# geiger-board.net
KiCad netlist of a schematic drawn in EAGLE
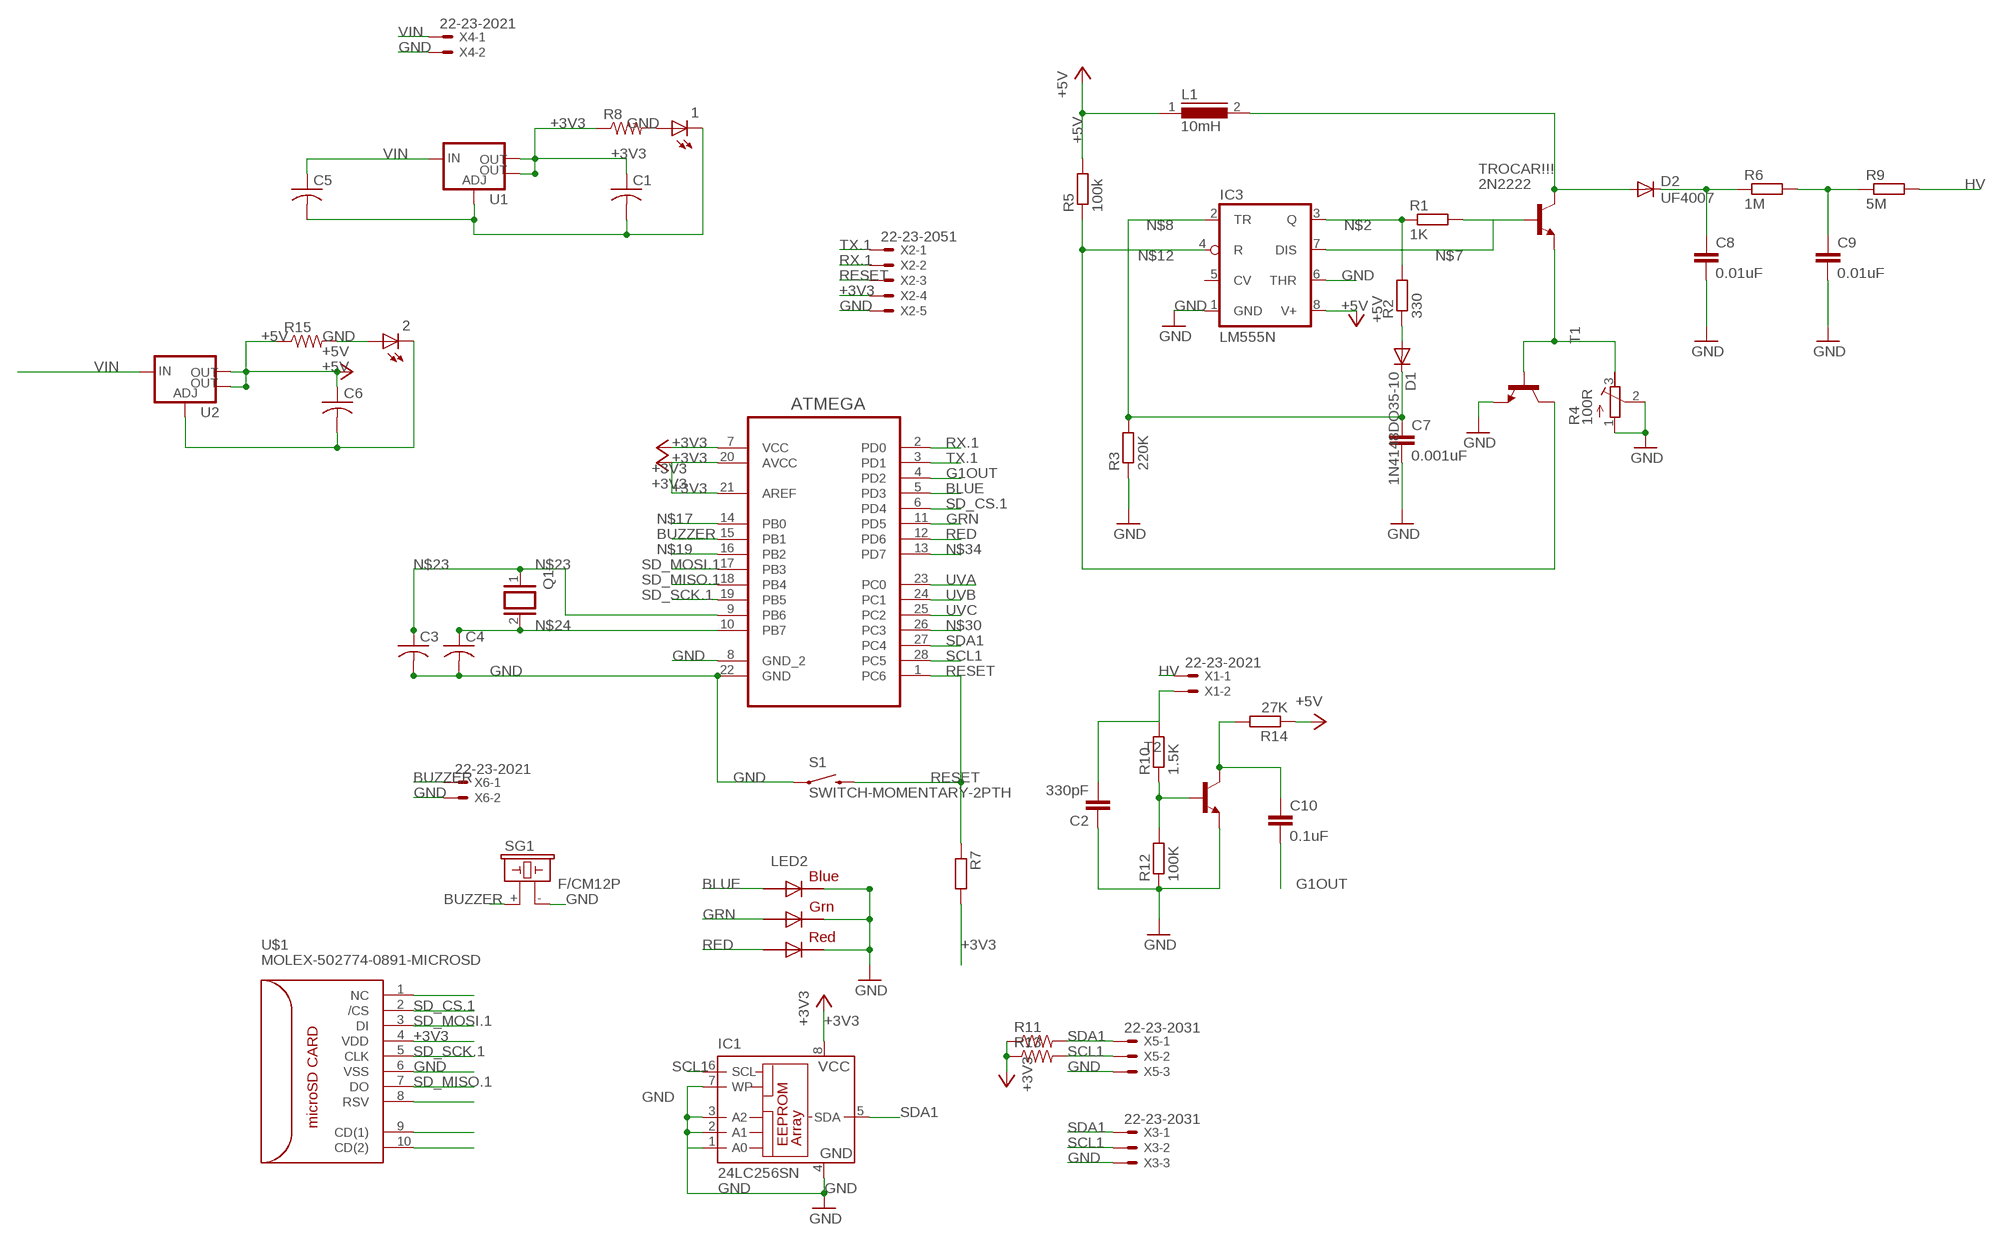
[diagram p0: schematic, sheet 1]

(export (version "E")
  (design (tool "Eeschema 10.0.6"))
  (components
    (comp (ref "1")
      (value "LEDSMT1206")
      (footprint "eagle-import:1206")
      (libsource (lib "eagle-import") (part "LEDSMT1206"))
    )
    (comp (ref "2")
      (value "LEDSMT1206")
      (footprint "eagle-import:1206")
      (libsource (lib "eagle-import") (part "LEDSMT1206"))
    )
    (comp (ref "ATMEGA")
      (value "ATMEGA328P-PU")
      (footprint "eagle-import:DIP254P762X457-28")
      (libsource (lib "eagle-import") (part "ATMEGA328P-PU"))
    )
    (comp (ref "C1")
      (value "C-USC1210K")
      (footprint "eagle-import:C1210K")
      (libsource (lib "eagle-import") (part "C-USC1210K"))
    )
    (comp (ref "C2")
      (value "330pF")
      (footprint "eagle-import:C5B4.5")
      (libsource (lib "eagle-import") (part "C5/4.5"))
    )
    (comp (ref "C3")
      (value "C-USC1210K")
      (footprint "eagle-import:C1210K")
      (libsource (lib "eagle-import") (part "C-USC1210K"))
    )
    (comp (ref "C4")
      (value "C-USC1210K")
      (footprint "eagle-import:C1210K")
      (libsource (lib "eagle-import") (part "C-USC1210K"))
    )
    (comp (ref "C5")
      (value "C-USC1210K")
      (footprint "eagle-import:C1210K")
      (libsource (lib "eagle-import") (part "C-USC1210K"))
    )
    (comp (ref "C6")
      (value "C-USC1210K")
      (footprint "eagle-import:C1210K")
      (libsource (lib "eagle-import") (part "C-USC1210K"))
    )
    (comp (ref "C7")
      (value "0.001uF")
      (footprint "eagle-import:C5B4.5")
      (libsource (lib "eagle-import") (part "C5/4.5"))
    )
    (comp (ref "C8")
      (value "0.01uF")
      (footprint "eagle-import:C5B4.5")
      (libsource (lib "eagle-import") (part "C5/4.5"))
    )
    (comp (ref "C9")
      (value "0.01uF")
      (footprint "eagle-import:C5B4.5")
      (libsource (lib "eagle-import") (part "C5/4.5"))
    )
    (comp (ref "C10")
      (value "0.1uF")
      (footprint "eagle-import:C5B4.5")
      (libsource (lib "eagle-import") (part "C5/4.5"))
    )
    (comp (ref "D1")
      (value "1N4148DO35-10")
      (footprint "eagle-import:DO35-10")
      (libsource (lib "eagle-import") (part "1N4148DO35-10"))
    )
    (comp (ref "D2")
      (value "UF4007")
      (footprint "eagle-import:DO35-10")
      (libsource (lib "eagle-import") (part "1N4148DO35-10"))
    )
    (comp (ref "IC1")
      (value "24LC256SN")
      (footprint "eagle-import:SO-08")
      (fields (field (name "MF") "MICROCHIP") (field (name "MPN") "24LC256-I/SN"))
      (libsource (lib "eagle-import") (part "24SNLC256"))
    )
    (comp (ref "IC3")
      (value "LM555N")
      (footprint "eagle-import:DIL08-ROUND")
      (libsource (lib "eagle-import") (part "555NLM"))
    )
    (comp (ref "L1")
      (value "10mH")
      (footprint "eagle-import:82114R")
      (libsource (lib "eagle-import") (part "82114R"))
    )
    (comp (ref "LED2")
      (value "RGBLED5050")
      (footprint "eagle-import:RGBLED5050")
      (libsource (lib "eagle-import") (part "RGBLED5050"))
    )
    (comp (ref "Q1")
      (value "XTAL/S")
      (footprint "eagle-import:QS")
      (libsource (lib "eagle-import") (part "XTAL/S"))
    )
    (comp (ref "R1")
      (value "1K")
      (footprint "eagle-import:0207_10")
      (libsource (lib "eagle-import") (part "R0207/10"))
    )
    (comp (ref "R2")
      (value "330")
      (footprint "eagle-import:0207_10")
      (libsource (lib "eagle-import") (part "R0207/10"))
    )
    (comp (ref "R3")
      (value "220K")
      (footprint "eagle-import:0207_10")
      (libsource (lib "eagle-import") (part "R0207/10"))
    )
    (comp (ref "R4")
      (value "100R")
      (footprint "eagle-import:RTRIM3296W")
      (libsource (lib "eagle-import") (part "R-TRIMM3296W"))
    )
    (comp (ref "R5")
      (value "100k")
      (footprint "eagle-import:0207_10")
      (libsource (lib "eagle-import") (part "R0207/10"))
    )
    (comp (ref "R6")
      (value "1M")
      (footprint "eagle-import:0207_10")
      (libsource (lib "eagle-import") (part "R0207/10"))
    )
    (comp (ref "R7")
      (value "R-EU_0207/10")
      (footprint "eagle-import:0207_10")
      (libsource (lib "eagle-import") (part "R-EU_0207/10"))
    )
    (comp (ref "R8")
      (value "R-US_M1206")
      (footprint "eagle-import:M1206")
      (libsource (lib "eagle-import") (part "R-US_M1206"))
    )
    (comp (ref "R9")
      (value "5M")
      (footprint "eagle-import:0207_10")
      (libsource (lib "eagle-import") (part "R0207/10"))
    )
    (comp (ref "R10")
      (value "1.5K")
      (footprint "eagle-import:0207_10")
      (libsource (lib "eagle-import") (part "R0207/10"))
    )
    (comp (ref "R11")
      (value "R-US_R1206")
      (footprint "eagle-import:R1206")
      (libsource (lib "eagle-import") (part "R-US_R1206"))
    )
    (comp (ref "R12")
      (value "100K")
      (footprint "eagle-import:0207_10")
      (libsource (lib "eagle-import") (part "R0207/10"))
    )
    (comp (ref "R13")
      (value "R-US_R1206")
      (footprint "eagle-import:R1206")
      (libsource (lib "eagle-import") (part "R-US_R1206"))
    )
    (comp (ref "R14")
      (value "27K")
      (footprint "eagle-import:0207_10")
      (libsource (lib "eagle-import") (part "R0207/10"))
    )
    (comp (ref "R15")
      (value "R-US_M1206")
      (footprint "eagle-import:M1206")
      (libsource (lib "eagle-import") (part "R-US_M1206"))
    )
    (comp (ref "S1")
      (value "SWITCH-MOMENTARY-2PTH")
      (footprint "eagle-import:TACTILE-PTH")
      (libsource (lib "eagle-import") (part "SWITCH-MOMENTARY-2PTH"))
    )
    (comp (ref "SG1")
      (value "F/CM12P")
      (footprint "eagle-import:F_CM12P")
      (libsource (lib "eagle-import") (part "F/CM12P"))
    )
    (comp (ref "T1")
      (value "2N4401-NPN-TO92-EBC")
      (footprint "eagle-import:TO92-EBC")
      (libsource (lib "eagle-import") (part "-NPN-TO92-EBC2N4401"))
    )
    (comp (ref "T2")
      (value "2N4401-NPN-TO92-EBC")
      (footprint "eagle-import:TO92-EBC")
      (libsource (lib "eagle-import") (part "-NPN-TO92-EBC2N4401"))
    )
    (comp (ref "TROCAR!!!")
      (value "2N2222")
      (footprint "eagle-import:TO92-EBC-OVAL")
      (libsource (lib "eagle-import") (part "2N2222"))
    )
    (comp (ref "U$1")
      (value "MOLEX-502774-0891-MICROSD")
      (footprint "eagle-import:MOLEX-502774-0891-MICROSD")
      (libsource (lib "eagle-import") (part "MOLEX-502774-0891-MICROSD"))
    )
    (comp (ref "U1")
      (value "V_REG_LM1117SOT223")
      (footprint "eagle-import:SOT223")
      (libsource (lib "eagle-import") (part "V_REG_LM1117SOT223"))
    )
    (comp (ref "U2")
      (value "V_REG_LM1117SOT223")
      (footprint "eagle-import:SOT223")
      (libsource (lib "eagle-import") (part "V_REG_LM1117SOT223"))
    )
    (comp (ref "X1")
      (value "22-23-2021")
      (footprint "eagle-import:22-23-2021")
      (fields (field (name "MF") "MOLEX"))
      (libsource (lib "eagle-import") (part "22-23-2021"))
    )
    (comp (ref "X2")
      (value "22-23-2051")
      (footprint "eagle-import:22-23-2051")
      (fields (field (name "MF") "MOLEX"))
      (libsource (lib "eagle-import") (part "22-23-2051"))
    )
    (comp (ref "X3")
      (value "22-23-2031")
      (footprint "eagle-import:22-23-2031")
      (fields (field (name "MF") "MOLEX"))
      (libsource (lib "eagle-import") (part "22-23-2031"))
    )
    (comp (ref "X4")
      (value "22-23-2021")
      (footprint "eagle-import:22-23-2021")
      (fields (field (name "MF") "MOLEX"))
      (libsource (lib "eagle-import") (part "22-23-2021"))
    )
    (comp (ref "X5")
      (value "22-23-2031")
      (footprint "eagle-import:22-23-2031")
      (fields (field (name "MF") "MOLEX"))
      (libsource (lib "eagle-import") (part "22-23-2031"))
    )
    (comp (ref "X6")
      (value "22-23-2021")
      (footprint "eagle-import:22-23-2021")
      (fields (field (name "MF") "MOLEX"))
      (libsource (lib "eagle-import") (part "22-23-2021"))
    )
  )
  (nets
    (net (code "1") (name "+3V3") (class "Default")
      (node (ref "ATMEGA") (pin "20") (pinfunction "AVCC_20") (pintype "power_in"))
      (node (ref "ATMEGA") (pin "21") (pinfunction "AREF_21") (pintype "input"))
      (node (ref "ATMEGA") (pin "7") (pinfunction "VCC_7") (pintype "power_in"))
      (node (ref "C1") (pin "1") (pinfunction "1_1") (pintype "passive"))
      (node (ref "IC1") (pin "8") (pinfunction "VCC_8") (pintype "power_in"))
      (node (ref "R11") (pin "1") (pinfunction "1_1") (pintype "passive"))
      (node (ref "R13") (pin "1") (pinfunction "1_1") (pintype "passive"))
      (node (ref "R7") (pin "2") (pinfunction "2_2") (pintype "passive"))
      (node (ref "R8") (pin "1") (pinfunction "1_1") (pintype "passive"))
      (node (ref "U$1") (pin "4") (pinfunction "VDD_4") (pintype "bidirectional"))
      (node (ref "U1") (pin "2") (pinfunction "OUT_2") (pintype "output"))
      (node (ref "U1") (pin "4") (pinfunction "OUT_4") (pintype "output"))
      (node (ref "X2") (pin "4") (pinfunction "S_4") (pintype "passive"))
    )
    (net (code "2") (name "+5V") (class "Default")
      (node (ref "C6") (pin "1") (pinfunction "1_1") (pintype "passive"))
      (node (ref "IC3") (pin "8") (pinfunction "V+_8") (pintype "power_in"))
      (node (ref "L1") (pin "1") (pinfunction "1_1") (pintype "passive"))
      (node (ref "R14") (pin "1") (pinfunction "1_1") (pintype "passive"))
      (node (ref "R15") (pin "1") (pinfunction "1_1") (pintype "passive"))
      (node (ref "R5") (pin "2") (pinfunction "2_2") (pintype "passive"))
      (node (ref "U2") (pin "2") (pinfunction "OUT_2") (pintype "output"))
      (node (ref "U2") (pin "4") (pinfunction "OUT_4") (pintype "output"))
    )
    (net (code "3") (name "/BLUE") (class "Default")
      (node (ref "ATMEGA") (pin "5") (pinfunction "PD3_5") (pintype "bidirectional"))
      (node (ref "LED2") (pin "3") (pinfunction "BLUE_A_3") (pintype "bidirectional"))
    )
    (net (code "4") (name "/BUZZER") (class "Default")
      (node (ref "ATMEGA") (pin "15") (pinfunction "PB1_15") (pintype "bidirectional"))
      (node (ref "SG1") (pin "+") (pinfunction "1_+") (pintype "passive"))
      (node (ref "X6") (pin "1") (pinfunction "S_1") (pintype "passive"))
    )
    (net (code "5") (name "/G1OUT") (class "Default")
      (node (ref "ATMEGA") (pin "4") (pinfunction "PD2_4") (pintype "bidirectional"))
      (node (ref "C10") (pin "2") (pinfunction "2_2") (pintype "passive"))
    )
    (net (code "6") (name "/GRN") (class "Default")
      (node (ref "ATMEGA") (pin "11") (pinfunction "PD5_11") (pintype "bidirectional"))
      (node (ref "LED2") (pin "1") (pinfunction "GREEN_A_1") (pintype "bidirectional"))
    )
    (net (code "7") (name "/HV") (class "Default")
      (node (ref "R9") (pin "2") (pinfunction "2_2") (pintype "passive"))
      (node (ref "X1") (pin "1") (pinfunction "S_1") (pintype "passive"))
    )
    (net (code "8") (name "/N$2") (class "Default")
      (node (ref "IC3") (pin "3") (pinfunction "Q_3") (pintype "output"))
      (node (ref "R1") (pin "1") (pinfunction "1_1") (pintype "passive"))
      (node (ref "R2") (pin "2") (pinfunction "2_2") (pintype "passive"))
    )
    (net (code "9") (name "/N$7") (class "Default")
      (node (ref "IC3") (pin "7") (pinfunction "DIS_7") (pintype "input"))
      (node (ref "R1") (pin "2") (pinfunction "2_2") (pintype "passive"))
      (node (ref "TROCAR!!!") (pin "B") (pinfunction "B_B") (pintype "passive"))
    )
    (net (code "10") (name "/N$8") (class "Default")
      (node (ref "C7") (pin "1") (pinfunction "1_1") (pintype "passive"))
      (node (ref "D1") (pin "C") (pinfunction "C_C") (pintype "passive"))
      (node (ref "IC3") (pin "2") (pinfunction "TR_2") (pintype "input"))
      (node (ref "R3") (pin "2") (pinfunction "2_2") (pintype "passive"))
    )
    (net (code "11") (name "/N$12") (class "Default")
      (node (ref "IC3") (pin "4") (pinfunction "R_4") (pintype "input"))
      (node (ref "R5") (pin "1") (pinfunction "1_1") (pintype "passive"))
      (node (ref "T1") (pin "C") (pinfunction "C_C") (pintype "passive"))
    )
    (net (code "12") (name "/N$17") (class "Default")
      (node (ref "ATMEGA") (pin "14") (pinfunction "PB0_14") (pintype "bidirectional"))
    )
    (net (code "13") (name "/N$19") (class "Default")
      (node (ref "ATMEGA") (pin "16") (pinfunction "PB2_16") (pintype "bidirectional"))
    )
    (net (code "14") (name "/N$23") (class "Default")
      (node (ref "ATMEGA") (pin "9") (pinfunction "PB6_9") (pintype "bidirectional"))
      (node (ref "C3") (pin "1") (pinfunction "1_1") (pintype "passive"))
      (node (ref "Q1") (pin "1") (pinfunction "1_1") (pintype "passive"))
    )
    (net (code "15") (name "/N$24") (class "Default")
      (node (ref "ATMEGA") (pin "10") (pinfunction "PB7_10") (pintype "bidirectional"))
      (node (ref "C4") (pin "1") (pinfunction "1_1") (pintype "passive"))
      (node (ref "Q1") (pin "2") (pinfunction "2_2") (pintype "passive"))
    )
    (net (code "16") (name "/N$30") (class "Default")
      (node (ref "ATMEGA") (pin "26") (pinfunction "PC3_26") (pintype "bidirectional"))
    )
    (net (code "17") (name "/N$34") (class "Default")
      (node (ref "ATMEGA") (pin "13") (pinfunction "PD7_13") (pintype "bidirectional"))
    )
    (net (code "18") (name "/RED") (class "Default")
      (node (ref "ATMEGA") (pin "12") (pinfunction "PD6_12") (pintype "bidirectional"))
      (node (ref "LED2") (pin "2") (pinfunction "RED_A_2") (pintype "bidirectional"))
    )
    (net (code "19") (name "/RESET") (class "Default")
      (node (ref "ATMEGA") (pin "1") (pinfunction "PC6_1") (pintype "bidirectional"))
      (node (ref "R7") (pin "1") (pinfunction "1_1") (pintype "passive"))
      (node (ref "S1") (pin "3") (pinfunction "2_3") (pintype "passive"))
      (node (ref "X2") (pin "3") (pinfunction "S_3") (pintype "passive"))
    )
    (net (code "20") (name "/RX.1") (class "Default")
      (node (ref "ATMEGA") (pin "2") (pinfunction "PD0_2") (pintype "bidirectional"))
      (node (ref "X2") (pin "2") (pinfunction "S_2") (pintype "passive"))
    )
    (net (code "21") (name "/SCL1") (class "Default")
      (node (ref "ATMEGA") (pin "28") (pinfunction "PC5_28") (pintype "bidirectional"))
      (node (ref "IC1") (pin "6") (pinfunction "SCL_6") (pintype "input"))
      (node (ref "R13") (pin "2") (pinfunction "2_2") (pintype "passive"))
      (node (ref "X3") (pin "2") (pinfunction "S_2") (pintype "passive"))
      (node (ref "X5") (pin "2") (pinfunction "S_2") (pintype "passive"))
    )
    (net (code "22") (name "/SDA1") (class "Default")
      (node (ref "ATMEGA") (pin "27") (pinfunction "PC4_27") (pintype "bidirectional"))
      (node (ref "IC1") (pin "5") (pinfunction "SDA_5") (pintype "bidirectional"))
      (node (ref "R11") (pin "2") (pinfunction "2_2") (pintype "passive"))
      (node (ref "X3") (pin "1") (pinfunction "S_1") (pintype "passive"))
      (node (ref "X5") (pin "1") (pinfunction "S_1") (pintype "passive"))
    )
    (net (code "23") (name "/SD_CS.1") (class "Default")
      (node (ref "ATMEGA") (pin "6") (pinfunction "PD4_6") (pintype "bidirectional"))
      (node (ref "U$1") (pin "2") (pinfunction "/CS_2") (pintype "bidirectional"))
    )
    (net (code "24") (name "/SD_MISO.1") (class "Default")
      (node (ref "ATMEGA") (pin "18") (pinfunction "PB4_18") (pintype "bidirectional"))
      (node (ref "U$1") (pin "7") (pinfunction "DO_7") (pintype "bidirectional"))
    )
    (net (code "25") (name "/SD_MOSI.1") (class "Default")
      (node (ref "ATMEGA") (pin "17") (pinfunction "PB3_17") (pintype "bidirectional"))
      (node (ref "U$1") (pin "3") (pinfunction "DI_3") (pintype "bidirectional"))
    )
    (net (code "26") (name "/SD_SCK.1") (class "Default")
      (node (ref "ATMEGA") (pin "19") (pinfunction "PB5_19") (pintype "bidirectional"))
      (node (ref "U$1") (pin "5") (pinfunction "CLK_5") (pintype "bidirectional"))
    )
    (net (code "27") (name "/TX.1") (class "Default")
      (node (ref "ATMEGA") (pin "3") (pinfunction "PD1_3") (pintype "bidirectional"))
      (node (ref "X2") (pin "1") (pinfunction "S_1") (pintype "passive"))
    )
    (net (code "28") (name "/UVA") (class "Default")
      (node (ref "ATMEGA") (pin "23") (pinfunction "PC0_23") (pintype "bidirectional"))
    )
    (net (code "29") (name "/UVB") (class "Default")
      (node (ref "ATMEGA") (pin "24") (pinfunction "PC1_24") (pintype "bidirectional"))
    )
    (net (code "30") (name "/UVC") (class "Default")
      (node (ref "ATMEGA") (pin "25") (pinfunction "PC2_25") (pintype "bidirectional"))
    )
    (net (code "31") (name "/VIN") (class "Default")
      (node (ref "C5") (pin "1") (pinfunction "1_1") (pintype "passive"))
      (node (ref "U1") (pin "3") (pinfunction "IN_3") (pintype "input"))
      (node (ref "U2") (pin "3") (pinfunction "IN_3") (pintype "input"))
      (node (ref "X4") (pin "1") (pinfunction "S_1") (pintype "passive"))
    )
    (net (code "32") (name "GND") (class "Default")
      (node (ref "1") (pin "C") (pinfunction "C_C") (pintype "passive"))
      (node (ref "2") (pin "C") (pinfunction "C_C") (pintype "passive"))
      (node (ref "ATMEGA") (pin "22") (pinfunction "GND_22") (pintype "passive"))
      (node (ref "ATMEGA") (pin "8") (pinfunction "GND_2_8") (pintype "passive"))
      (node (ref "C1") (pin "2") (pinfunction "2_2") (pintype "passive"))
      (node (ref "C2") (pin "1") (pinfunction "1_1") (pintype "passive"))
      (node (ref "C3") (pin "2") (pinfunction "2_2") (pintype "passive"))
      (node (ref "C4") (pin "2") (pinfunction "2_2") (pintype "passive"))
      (node (ref "C5") (pin "2") (pinfunction "2_2") (pintype "passive"))
      (node (ref "C6") (pin "2") (pinfunction "2_2") (pintype "passive"))
      (node (ref "C7") (pin "2") (pinfunction "2_2") (pintype "passive"))
      (node (ref "C8") (pin "2") (pinfunction "2_2") (pintype "passive"))
      (node (ref "C9") (pin "2") (pinfunction "2_2") (pintype "passive"))
      (node (ref "IC1") (pin "1") (pinfunction "A0_1") (pintype "input"))
      (node (ref "IC1") (pin "2") (pinfunction "A1_2") (pintype "input"))
      (node (ref "IC1") (pin "3") (pinfunction "A2_3") (pintype "input"))
      (node (ref "IC1") (pin "4") (pinfunction "GND_4") (pintype "power_in"))
      (node (ref "IC1") (pin "7") (pinfunction "WP_7") (pintype "input"))
      (node (ref "IC3") (pin "1") (pinfunction "GND_1") (pintype "power_in"))
      (node (ref "IC3") (pin "6") (pinfunction "THR_6") (pintype "input"))
      (node (ref "LED2") (pin "4") (pinfunction "BLUE_C_4") (pintype "bidirectional"))
      (node (ref "LED2") (pin "5") (pinfunction "RED_C_5") (pintype "bidirectional"))
      (node (ref "LED2") (pin "6") (pinfunction "GREEN_C_6") (pintype "bidirectional"))
      (node (ref "R12") (pin "1") (pinfunction "1_1") (pintype "passive"))
      (node (ref "R3") (pin "1") (pinfunction "1_1") (pintype "passive"))
      (node (ref "R4") (pin "1") (pinfunction "A_1") (pintype "passive"))
      (node (ref "R4") (pin "2") (pinfunction "S_2") (pintype "passive"))
      (node (ref "S1") (pin "1") (pinfunction "1_1") (pintype "passive"))
      (node (ref "SG1") (pin "-") (pinfunction "2_-") (pintype "passive"))
      (node (ref "T1") (pin "E") (pinfunction "E_E") (pintype "passive"))
      (node (ref "T2") (pin "E") (pinfunction "E_E") (pintype "passive"))
      (node (ref "U$1") (pin "6") (pinfunction "VSS_6") (pintype "bidirectional"))
      (node (ref "U1") (pin "1") (pinfunction "ADJ_1") (pintype "input"))
      (node (ref "U2") (pin "1") (pinfunction "ADJ_1") (pintype "input"))
      (node (ref "X2") (pin "5") (pinfunction "S_5") (pintype "passive"))
      (node (ref "X3") (pin "3") (pinfunction "S_3") (pintype "passive"))
      (node (ref "X4") (pin "2") (pinfunction "S_2") (pintype "passive"))
      (node (ref "X5") (pin "3") (pinfunction "S_3") (pintype "passive"))
      (node (ref "X6") (pin "2") (pinfunction "S_2") (pintype "passive"))
    )
    (net (code "33") (name "Net-(1-PadA)") (class "Default")
      (node (ref "1") (pin "A") (pinfunction "A_A") (pintype "passive"))
      (node (ref "R8") (pin "2") (pinfunction "2_2") (pintype "passive"))
    )
    (net (code "34") (name "Net-(2-PadA)") (class "Default")
      (node (ref "2") (pin "A") (pinfunction "A_A") (pintype "passive"))
      (node (ref "R15") (pin "2") (pinfunction "2_2") (pintype "passive"))
    )
    (net (code "35") (name "Net-(C8-Pad1)") (class "Default")
      (node (ref "C8") (pin "1") (pinfunction "1_1") (pintype "passive"))
      (node (ref "D2") (pin "C") (pinfunction "C_C") (pintype "passive"))
      (node (ref "R6") (pin "1") (pinfunction "1_1") (pintype "passive"))
    )
    (net (code "36") (name "Net-(C9-Pad1)") (class "Default")
      (node (ref "C9") (pin "1") (pinfunction "1_1") (pintype "passive"))
      (node (ref "R6") (pin "2") (pinfunction "2_2") (pintype "passive"))
      (node (ref "R9") (pin "1") (pinfunction "1_1") (pintype "passive"))
    )
    (net (code "37") (name "Net-(C10-Pad1)") (class "Default")
      (node (ref "C10") (pin "1") (pinfunction "1_1") (pintype "passive"))
      (node (ref "R14") (pin "2") (pinfunction "2_2") (pintype "passive"))
      (node (ref "T2") (pin "C") (pinfunction "C_C") (pintype "passive"))
    )
    (net (code "38") (name "Net-(D1-PadA)") (class "Default")
      (node (ref "D1") (pin "A") (pinfunction "A_A") (pintype "passive"))
      (node (ref "R2") (pin "1") (pinfunction "1_1") (pintype "passive"))
    )
    (net (code "39") (name "Net-(D2-PadA)") (class "Default")
      (node (ref "D2") (pin "A") (pinfunction "A_A") (pintype "passive"))
      (node (ref "L1") (pin "2") (pinfunction "2_2") (pintype "passive"))
      (node (ref "TROCAR!!!") (pin "C") (pinfunction "C_C") (pintype "passive"))
    )
    (net (code "40") (name "Net-(R4-E)") (class "Default")
      (node (ref "R4") (pin "3") (pinfunction "E_3") (pintype "passive"))
      (node (ref "T1") (pin "B") (pinfunction "B_B") (pintype "passive"))
      (node (ref "TROCAR!!!") (pin "E") (pinfunction "E_E") (pintype "passive"))
    )
    (net (code "41") (name "Net-(R10-Pad1)") (class "Default")
      (node (ref "R10") (pin "1") (pinfunction "1_1") (pintype "passive"))
      (node (ref "R12") (pin "2") (pinfunction "2_2") (pintype "passive"))
      (node (ref "T2") (pin "B") (pinfunction "B_B") (pintype "passive"))
    )
    (net (code "42") (name "Net-(X1B-S)") (class "Default")
      (node (ref "C2") (pin "2") (pinfunction "2_2") (pintype "passive"))
      (node (ref "R10") (pin "2") (pinfunction "2_2") (pintype "passive"))
      (node (ref "X1") (pin "2") (pinfunction "S_2") (pintype "passive"))
    )
    (net (code "43") (name "unconnected-(IC3-CV-Pad5)") (class "Default")
      (node (ref "IC3") (pin "5") (pinfunction "CV_5") (pintype "input"))
    )
    (net (code "44") (name "unconnected-(U$1-CD(1)-Pad9)") (class "Default")
      (node (ref "U$1") (pin "9") (pinfunction "CD(1)_9") (pintype "bidirectional"))
    )
    (net (code "45") (name "unconnected-(U$1-CD(2)-Pad10)") (class "Default")
      (node (ref "U$1") (pin "10") (pinfunction "CD(2)_10") (pintype "bidirectional"))
    )
    (net (code "46") (name "unconnected-(U$1-NC-Pad1)") (class "Default")
      (node (ref "U$1") (pin "1") (pinfunction "NC_1") (pintype "bidirectional"))
    )
    (net (code "47") (name "unconnected-(U$1-RSV-Pad8)") (class "Default")
      (node (ref "U$1") (pin "8") (pinfunction "RSV_8") (pintype "bidirectional"))
    )
  )
)
